# Controller_driver.net
KiCad netlist of a schematic drawn in Altium Designer
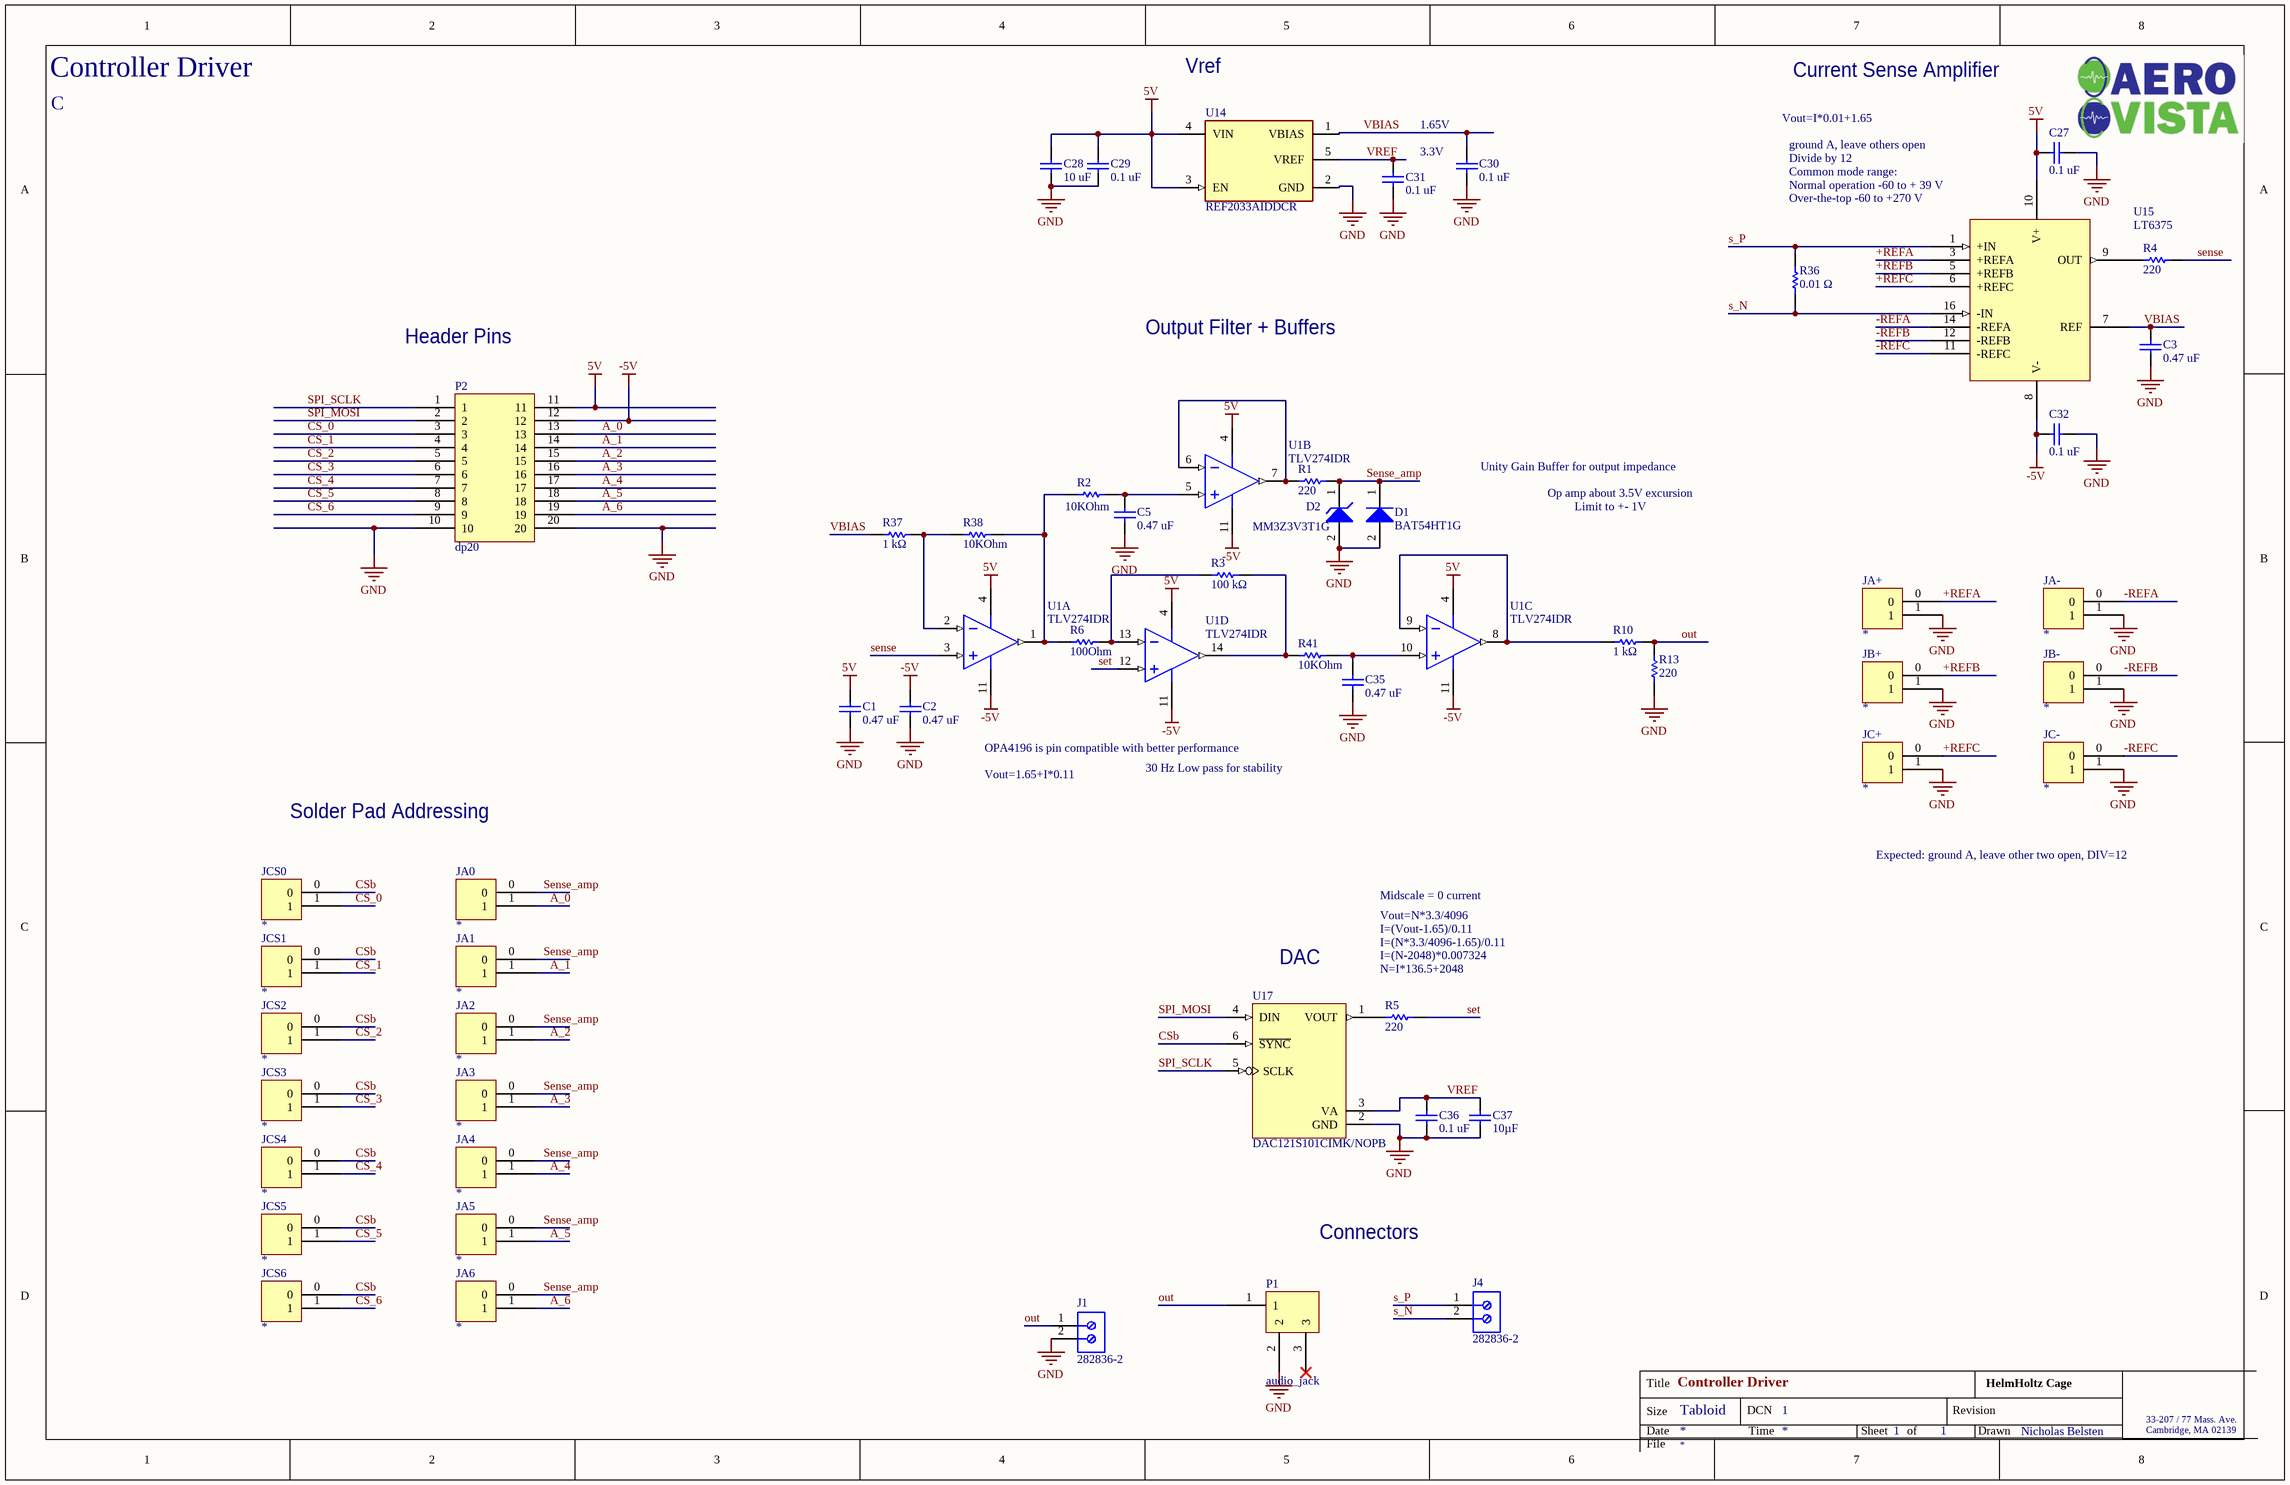
[diagram p0: Controller_driver.SchDoc]

(export (version "E")
  (design (tool "Eeschema 10.0.6"))
  (components
    (comp (ref "C1")
      (value "0.47 uF")
      (footprint "CAPC1608X90X35ML10T15")
      (fields (field (name "MANUFACTURER") "Murata") (field (name "PART NUMBER") "GRM188R71C474KA88D"))
      (libsource (lib "Altium Content Vault") (part "CAP"))
    )
    (comp (ref "C2")
      (value "0.47 uF")
      (footprint "CAPC1608X90X35ML10T15")
      (fields (field (name "MANUFACTURER") "Murata") (field (name "PART NUMBER") "GRM188R71C474KA88D"))
      (libsource (lib "Altium Content Vault") (part "CAP"))
    )
    (comp (ref "C3")
      (value "0.47 uF")
      (footprint "CAPC1608X90X35ML10T15")
      (fields (field (name "MANUFACTURER") "Murata") (field (name "PART NUMBER") "GRM188R71C474KA88D"))
      (libsource (lib "Altium Content Vault") (part "CAP"))
    )
    (comp (ref "C5")
      (value "0.47 uF")
      (footprint "CAPC1608X90X35ML10T15")
      (fields (field (name "MANUFACTURER") "Murata") (field (name "PART NUMBER") "GRM188R71C474KA88D"))
      (libsource (lib "Altium Content Vault") (part "CAP"))
    )
    (comp (ref "C27")
      (value "0.1 uF")
      (footprint "CAPC1608X87X35NL15T15")
      (fields (field (name "PART NUMBER") "C0603X104K5RACTU") (field (name "MANUFACTURER") "Kemet"))
      (libsource (lib "Altium Content Vault") (part "CAP"))
    )
    (comp (ref "C28")
      (value "10 uF")
      (footprint "CAPC1608X90X20ML10")
      (description "Chip Capacitor, 10 uF, +/- 10%, 10 V, -55 to 85 degC, 0603 (1608 Metric), RoHS, Tape and Reel")
      (fields
        (field (name "PCN PART NUMBER") "MLCCPartNumberChange30/Nov/2012")
        (field (name "TOLERANCE") "±10%")
      )
      (libsource (lib "Altium Content Vault") (part "CAP-NP-2"))
    )
    (comp (ref "C29")
      (value "0.1 uF")
      (footprint "CAPC1608X87X35NL15T15")
      (fields (field (name "PART NUMBER") "C0603X104K5RACTU") (field (name "MANUFACTURER") "Kemet"))
      (libsource (lib "Altium Content Vault") (part "CAP"))
    )
    (comp (ref "C30")
      (value "0.1 uF")
      (footprint "CAPC1608X87X35NL15T15")
      (fields (field (name "PART NUMBER") "C0603X104K5RACTU") (field (name "MANUFACTURER") "Kemet"))
      (libsource (lib "Altium Content Vault") (part "CAP"))
    )
    (comp (ref "C31")
      (value "0.1 uF")
      (footprint "CAPC1608X87X35NL15T15")
      (fields (field (name "PART NUMBER") "C0603X104K5RACTU") (field (name "MANUFACTURER") "Kemet"))
      (libsource (lib "Altium Content Vault") (part "CAP"))
    )
    (comp (ref "C32")
      (value "0.1 uF")
      (footprint "CAPC1608X87X35NL15T15")
      (fields (field (name "PART NUMBER") "C0603X104K5RACTU") (field (name "MANUFACTURER") "Kemet"))
      (libsource (lib "Altium Content Vault") (part "CAP"))
    )
    (comp (ref "C35")
      (value "0.47 uF")
      (footprint "CAPC1608X90X35ML10T15")
      (fields (field (name "MANUFACTURER") "Murata") (field (name "PART NUMBER") "GRM188R71C474KA88D"))
      (libsource (lib "Altium Content Vault") (part "CAP"))
    )
    (comp (ref "C36")
      (value "0.1 uF")
      (footprint "CAPC1608X87X35NL15T15")
      (fields (field (name "PART NUMBER") "C0603X104K5RACTU") (field (name "MANUFACTURER") "Kemet"))
      (libsource (lib "Altium Content Vault") (part "CAP"))
    )
    (comp (ref "C37")
      (value "10µF")
      (footprint "CAPC1608X90X20ML10")
      (description "Chip Capacitor, 10 uF, +/- 10%, 10 V, -55 to 85 degC, 0603 (1608 Metric), RoHS, Tape and Reel")
      (fields
        (field (name "PCN PART NUMBER") "MLCCPartNumberChange30/Nov/2012")
        (field (name "TOLERANCE") "±10%")
      )
      (libsource (lib "Altium Content Vault") (part "CAP-NP-2"))
    )
    (comp (ref "D1")
      (value "BAT54HT1G")
      (footprint "ONSC-SOD-323-2-477-02_V")
      (description "Schottky Barrier Diode, 2-Pin SOD-323, Pb-Free, Tape and Reel")
      (fields (field (name "MANUFACTURER") "On Semiconductor"))
      (libsource (lib "Altium Content Vault") (part "ONSC-D-K1A2-2"))
    )
    (comp (ref "D2")
      (value "MM3Z3V3T1G")
      (footprint "ONSC-SOD-323-2-477-02_V")
      (description "Zener Voltage Regulator, 300 mW, 2-Pin SOD-323, Pb-Free, Tape and Reel")
      (fields (field (name "MANUFACTURER") "On Semiconductor"))
      (libsource (lib "Altium Content Vault") (part "ONSC-K1A2-2"))
    )
    (comp (ref "J1")
      (value "282836-2")
      (footprint "TECO-282836-2_V")
      (description "Female Header, Pitch 5 mm, 1 x 2 Position, Height 10 mm, Tail Length 3.5 mm, Rohs, Bulk")
      (fields (field (name "VOLTAGE") "300V") (field (name "MANUFACTURER") "TE Connectivity"))
      (libsource (lib "Altium Content Vault") (part "CN-1P-F-TB2"))
    )
    (comp (ref "J4")
      (value "282836-2")
      (footprint "TECO-282836-2_V")
      (description "Female Header, Pitch 5 mm, 1 x 2 Position, Height 10 mm, Tail Length 3.5 mm, Rohs, Bulk")
      (fields (field (name "VOLTAGE") "300V") (field (name "MANUFACTURER") "TE Connectivity"))
      (libsource (lib "Altium Content Vault") (part "CN-1P-F-TB2"))
    )
    (comp (ref "JA+") (value "*") (footprint "solder_jumper") (libsource (lib "*") (part "solder_jumper")))
    (comp (ref "JA-") (value "*") (footprint "solder_jumper") (libsource (lib "*") (part "solder_jumper")))
    (comp (ref "JA0") (value "*") (footprint "solder_jumper") (libsource (lib "*") (part "solder_jumper")))
    (comp (ref "JA1") (value "*") (footprint "solder_jumper") (libsource (lib "*") (part "solder_jumper")))
    (comp (ref "JA2") (value "*") (footprint "solder_jumper") (libsource (lib "*") (part "solder_jumper")))
    (comp (ref "JA3") (value "*") (footprint "solder_jumper") (libsource (lib "*") (part "solder_jumper")))
    (comp (ref "JA4") (value "*") (footprint "solder_jumper") (libsource (lib "*") (part "solder_jumper")))
    (comp (ref "JA5") (value "*") (footprint "solder_jumper") (libsource (lib "*") (part "solder_jumper")))
    (comp (ref "JA6") (value "*") (footprint "solder_jumper") (libsource (lib "*") (part "solder_jumper")))
    (comp (ref "JB+") (value "*") (footprint "solder_jumper") (libsource (lib "*") (part "solder_jumper")))
    (comp (ref "JB-") (value "*") (footprint "solder_jumper") (libsource (lib "*") (part "solder_jumper")))
    (comp (ref "JC+") (value "*") (footprint "solder_jumper") (libsource (lib "*") (part "solder_jumper")))
    (comp (ref "JC-") (value "*") (footprint "solder_jumper") (libsource (lib "*") (part "solder_jumper")))
    (comp (ref "JCS0") (value "*") (footprint "solder_jumper") (libsource (lib "*") (part "solder_jumper")))
    (comp (ref "JCS1") (value "*") (footprint "solder_jumper") (libsource (lib "*") (part "solder_jumper")))
    (comp (ref "JCS2") (value "*") (footprint "solder_jumper") (libsource (lib "*") (part "solder_jumper")))
    (comp (ref "JCS3") (value "*") (footprint "solder_jumper") (libsource (lib "*") (part "solder_jumper")))
    (comp (ref "JCS4") (value "*") (footprint "solder_jumper") (libsource (lib "*") (part "solder_jumper")))
    (comp (ref "JCS5") (value "*") (footprint "solder_jumper") (libsource (lib "*") (part "solder_jumper")))
    (comp (ref "JCS6") (value "*") (footprint "solder_jumper") (libsource (lib "*") (part "solder_jumper")))
    (comp (ref "P1")
      (value "audio_jack")
      (footprint "MJ-3536NG")
      (libsource (lib "myComponents") (part "audio_jack"))
    )
    (comp (ref "P2")
      (value "dp20")
      (footprint "dp20-900-double")
      (libsource (lib "myComponents") (part "dp20"))
    )
    (comp (ref "R1")
      (value "220")
      (footprint "RESC1609X50X30LL10T20")
      (fields (field (name "PART NUMBER") "CRCW0603220RFKEA") (field (name "MANUFACTURER") "Vishay Dale"))
      (libsource (lib "Altium Content Vault") (part "RES"))
    )
    (comp (ref "R2")
      (value "10KOhm")
      (footprint "RESC1609X55X30LL15T15")
      (description "Chip Resistor, 10 KOhm, +/- 1%, 0.1 W, -55 to 155 degC, 0603 (1608 Metric), RoHS, Tape and Reel")
      (fields (field (name "TOLERANCE") "1%") (field (name "MANUFACTURER") "Panasonic"))
      (libsource (lib "Altium Content Vault") (part "RES-2"))
    )
    (comp (ref "R3")
      (value "100 kΩ")
      (footprint "RESC1608X55X25NL10T15")
      (fields (field (name "PART NUMBER") "RC0603JR-10100KL") (field (name "MANUFACTURER") "Yageo"))
      (libsource (lib "Altium Content Vault") (part "RES"))
    )
    (comp (ref "R4")
      (value "220")
      (footprint "RESC1609X50X30LL10T20")
      (fields (field (name "PART NUMBER") "CRCW0603220RFKEA") (field (name "MANUFACTURER") "Vishay Dale"))
      (libsource (lib "Altium Content Vault") (part "RES"))
    )
    (comp (ref "R5")
      (value "220")
      (footprint "RESC1609X50X30LL10T20")
      (fields (field (name "PART NUMBER") "CRCW0603220RFKEA") (field (name "MANUFACTURER") "Vishay Dale"))
      (libsource (lib "Altium Content Vault") (part "RES"))
    )
    (comp (ref "R6")
      (value "100Ohm")
      (footprint "RESC1608X55X25NL10T15")
      (description "Chip Resistor, 100 Ohm, +/- 1%, 0.1 W, -55 to 155 degC, 0603 (1608 Metric), RoHS, Tape and Reel")
      (fields (field (name "TOLERANCE") "1%") (field (name "MANUFACTURER") "Yageo"))
      (libsource (lib "Altium Content Vault") (part "RES-2"))
    )
    (comp (ref "R10")
      (value "1 kΩ")
      (footprint "RESC1608X55X30LL20T20")
      (fields (field (name "MANUFACTURER") "Panasonic") (field (name "PART NUMBER") "ERA3AEB102V"))
      (libsource (lib "Altium Content Vault") (part "RES"))
    )
    (comp (ref "R13")
      (value "220")
      (footprint "RESC1609X50X30LL10T20")
      (fields (field (name "PART NUMBER") "CRCW0603220RFKEA") (field (name "MANUFACTURER") "Vishay Dale"))
      (libsource (lib "Altium Content Vault") (part "RES"))
    )
    (comp (ref "R36")
      (value "0.01 Ω")
      (footprint "RESC3216X70X50LL05T20")
      (fields (field (name "PART NUMBER") "ERJ8BWFR010V") (field (name "MANUFACTURER") "Panasonic"))
      (libsource (lib "Altium Content Vault") (part "RES"))
    )
    (comp (ref "R37")
      (value "1 kΩ")
      (footprint "RESC1608X55X30LL15T15")
      (fields (field (name "PART NUMBER") "ERJ-3EKF1001V") (field (name "MANUFACTURER") "Panasonic"))
      (libsource (lib "Altium Content Vault") (part "RES"))
    )
    (comp (ref "R38")
      (value "10KOhm")
      (footprint "RESC1609X55X30LL15T15")
      (description "Chip Resistor, 10 KOhm, +/- 1%, 0.1 W, -55 to 155 degC, 0603 (1608 Metric), RoHS, Tape and Reel")
      (fields (field (name "TOLERANCE") "1%") (field (name "MANUFACTURER") "Panasonic"))
      (libsource (lib "Altium Content Vault") (part "RES-2"))
    )
    (comp (ref "R41")
      (value "10KOhm")
      (footprint "RESC1609X55X30LL15T15")
      (description "Chip Resistor, 10 KOhm, +/- 1%, 0.1 W, -55 to 155 degC, 0603 (1608 Metric), RoHS, Tape and Reel")
      (fields (field (name "TOLERANCE") "1%") (field (name "MANUFACTURER") "Panasonic"))
      (libsource (lib "Altium Content Vault") (part "RES-2"))
    )
    (comp (ref "U1")
      (value "TLV274IDR")
      (footprint "D0014A_N")
      (fields (field (name "MANUFACTURER") "Texas Instruments"))
      (libsource (lib "Altium Content Vault") (part "TI-TLC_TLV_TLC1079-14"))
    )
    (comp (ref "U14")
      (value "REF2033AIDDCR")
      (footprint "FP-DDC0005A-MFG")
      (description "IC VREF SERIES 1.65V/3.3V 5SOT")
      (fields
        (field (name "OCTOPART") "https://octopart.com/ref2033aiddcr-texas+instruments-46921199")
        (field (name "MANUFACTURER") "Texas Instruments")
      )
      (libsource (lib "Altium Content Vault") (part "d9fc07eafd300fec854b4093a15f761"))
    )
    (comp (ref "U15")
      (value "LT6375")
      (footprint "SOP16-12")
      (libsource (lib "myComponents") (part "LT6375"))
    )
    (comp (ref "U17")
      (value "DAC121S101CIMK/NOPB")
      (footprint "MK06A_N")
      (description "12-Bit Micro Power, RRO Digital-to-Analog Converter, 6-pin Tiny SOT23, Pb-Free")
      (fields (field (name "MANUFACTURER") "National Semiconductor"))
      (libsource (lib "Altium Content Vault") (part "CON-DAC-DAC121S101-6"))
    )
  )
  (nets
    (net (code "1") (name "-5V") (class "Default")
      (node (ref "C2") (pin "2") (pinfunction "2_2") (pintype "passive"))
      (node (ref "C32") (pin "2") (pinfunction "2_2") (pintype "passive"))
      (node (ref "P2") (pin "12") (pinfunction "12_12") (pintype "passive"))
      (node (ref "U1") (pin "11") (pinfunction "GND_11") (pintype "power_in"))
      (node (ref "U15") (pin "8") (pinfunction "V-_8") (pintype "power_in"))
    )
    (net (code "2") (name "/+REFA") (class "Default")
      (node (ref "JA+") (pin "0") (pinfunction "0_0") (pintype "passive"))
      (node (ref "U15") (pin "3") (pinfunction "+REFA_3") (pintype "passive"))
    )
    (net (code "3") (name "/+REFB") (class "Default")
      (node (ref "JB+") (pin "0") (pinfunction "0_0") (pintype "passive"))
      (node (ref "U15") (pin "5") (pinfunction "+REFB_5") (pintype "passive"))
    )
    (net (code "4") (name "/+REFC") (class "Default")
      (node (ref "JC+") (pin "0") (pinfunction "0_0") (pintype "passive"))
      (node (ref "U15") (pin "6") (pinfunction "+REFC_6") (pintype "passive"))
    )
    (net (code "5") (name "/-REFA") (class "Default")
      (node (ref "JA-") (pin "0") (pinfunction "0_0") (pintype "passive"))
      (node (ref "U15") (pin "14") (pinfunction "-REFA_14") (pintype "passive"))
    )
    (net (code "6") (name "/-REFB") (class "Default")
      (node (ref "JB-") (pin "0") (pinfunction "0_0") (pintype "passive"))
      (node (ref "U15") (pin "12") (pinfunction "-REFB_12") (pintype "passive"))
    )
    (net (code "7") (name "/-REFC") (class "Default")
      (node (ref "JC-") (pin "0") (pinfunction "0_0") (pintype "passive"))
      (node (ref "U15") (pin "11") (pinfunction "-REFC_11") (pintype "passive"))
    )
    (net (code "8") (name "/A_0") (class "Default")
      (node (ref "JA0") (pin "1") (pinfunction "1_1") (pintype "passive"))
      (node (ref "P2") (pin "13") (pinfunction "13_13") (pintype "passive"))
    )
    (net (code "9") (name "/A_1") (class "Default")
      (node (ref "JA1") (pin "1") (pinfunction "1_1") (pintype "passive"))
      (node (ref "P2") (pin "14") (pinfunction "14_14") (pintype "passive"))
    )
    (net (code "10") (name "/A_2") (class "Default")
      (node (ref "JA2") (pin "1") (pinfunction "1_1") (pintype "passive"))
      (node (ref "P2") (pin "15") (pinfunction "15_15") (pintype "passive"))
    )
    (net (code "11") (name "/A_3") (class "Default")
      (node (ref "JA3") (pin "1") (pinfunction "1_1") (pintype "passive"))
      (node (ref "P2") (pin "16") (pinfunction "16_16") (pintype "passive"))
    )
    (net (code "12") (name "/A_4") (class "Default")
      (node (ref "JA4") (pin "1") (pinfunction "1_1") (pintype "passive"))
      (node (ref "P2") (pin "17") (pinfunction "17_17") (pintype "passive"))
    )
    (net (code "13") (name "/A_5") (class "Default")
      (node (ref "JA5") (pin "1") (pinfunction "1_1") (pintype "passive"))
      (node (ref "P2") (pin "18") (pinfunction "18_18") (pintype "passive"))
    )
    (net (code "14") (name "/A_6") (class "Default")
      (node (ref "JA6") (pin "1") (pinfunction "1_1") (pintype "passive"))
      (node (ref "P2") (pin "19") (pinfunction "19_19") (pintype "passive"))
    )
    (net (code "15") (name "/CS_0") (class "Default")
      (node (ref "JCS0") (pin "1") (pinfunction "1_1") (pintype "passive"))
      (node (ref "P2") (pin "3") (pinfunction "3_3") (pintype "passive"))
    )
    (net (code "16") (name "/CS_1") (class "Default")
      (node (ref "JCS1") (pin "1") (pinfunction "1_1") (pintype "passive"))
      (node (ref "P2") (pin "4") (pinfunction "4_4") (pintype "passive"))
    )
    (net (code "17") (name "/CS_2") (class "Default")
      (node (ref "JCS2") (pin "1") (pinfunction "1_1") (pintype "passive"))
      (node (ref "P2") (pin "5") (pinfunction "5_5") (pintype "passive"))
    )
    (net (code "18") (name "/CS_3") (class "Default")
      (node (ref "JCS3") (pin "1") (pinfunction "1_1") (pintype "passive"))
      (node (ref "P2") (pin "6") (pinfunction "6_6") (pintype "passive"))
    )
    (net (code "19") (name "/CS_4") (class "Default")
      (node (ref "JCS4") (pin "1") (pinfunction "1_1") (pintype "passive"))
      (node (ref "P2") (pin "7") (pinfunction "7_7") (pintype "passive"))
    )
    (net (code "20") (name "/CS_5") (class "Default")
      (node (ref "JCS5") (pin "1") (pinfunction "1_1") (pintype "passive"))
      (node (ref "P2") (pin "8") (pinfunction "8_8") (pintype "passive"))
    )
    (net (code "21") (name "/CS_6") (class "Default")
      (node (ref "JCS6") (pin "1") (pinfunction "1_1") (pintype "passive"))
      (node (ref "P2") (pin "9") (pinfunction "9_9") (pintype "passive"))
    )
    (net (code "22") (name "/CSb") (class "Default")
      (node (ref "JCS0") (pin "0") (pinfunction "0_0") (pintype "passive"))
      (node (ref "JCS1") (pin "0") (pinfunction "0_0") (pintype "passive"))
      (node (ref "JCS2") (pin "0") (pinfunction "0_0") (pintype "passive"))
      (node (ref "JCS3") (pin "0") (pinfunction "0_0") (pintype "passive"))
      (node (ref "JCS4") (pin "0") (pinfunction "0_0") (pintype "passive"))
      (node (ref "JCS5") (pin "0") (pinfunction "0_0") (pintype "passive"))
      (node (ref "JCS6") (pin "0") (pinfunction "0_0") (pintype "passive"))
      (node (ref "U17") (pin "6") (pinfunction "~{SYNC}_6") (pintype "input"))
    )
    (net (code "23") (name "/SPI_MOSI") (class "Default")
      (node (ref "P2") (pin "2") (pinfunction "2_2") (pintype "passive"))
      (node (ref "U17") (pin "4") (pinfunction "DIN_4") (pintype "input"))
    )
    (net (code "24") (name "/SPI_SCLK") (class "Default")
      (node (ref "P2") (pin "1") (pinfunction "1_1") (pintype "passive"))
      (node (ref "U17") (pin "5") (pinfunction "SCLK_5") (pintype "input"))
    )
    (net (code "25") (name "/Sense_amp") (class "Default")
      (node (ref "D1") (pin "1") (pinfunction "K_1") (pintype "passive"))
      (node (ref "D2") (pin "1") (pinfunction "K_1") (pintype "passive"))
      (node (ref "JA0") (pin "0") (pinfunction "0_0") (pintype "passive"))
      (node (ref "JA1") (pin "0") (pinfunction "0_0") (pintype "passive"))
      (node (ref "JA2") (pin "0") (pinfunction "0_0") (pintype "passive"))
      (node (ref "JA3") (pin "0") (pinfunction "0_0") (pintype "passive"))
      (node (ref "JA4") (pin "0") (pinfunction "0_0") (pintype "passive"))
      (node (ref "JA5") (pin "0") (pinfunction "0_0") (pintype "passive"))
      (node (ref "JA6") (pin "0") (pinfunction "0_0") (pintype "passive"))
      (node (ref "R1") (pin "2") (pinfunction "2_2") (pintype "passive"))
    )
    (net (code "26") (name "/VBIAS") (class "Default")
      (node (ref "C3") (pin "2") (pinfunction "2_2") (pintype "passive"))
      (node (ref "C30") (pin "2") (pinfunction "2_2") (pintype "passive"))
      (node (ref "R37") (pin "2") (pinfunction "2_2") (pintype "passive"))
      (node (ref "U14") (pin "1") (pinfunction "VBIAS_1") (pintype "power_in"))
      (node (ref "U15") (pin "7") (pinfunction "REF_7") (pintype "passive"))
    )
    (net (code "27") (name "/VREF") (class "Default")
      (node (ref "C31") (pin "2") (pinfunction "2_2") (pintype "passive"))
      (node (ref "C36") (pin "2") (pinfunction "2_2") (pintype "passive"))
      (node (ref "C37") (pin "2") (pinfunction "2_2") (pintype "passive"))
      (node (ref "U14") (pin "5") (pinfunction "VREF_5") (pintype "power_in"))
      (node (ref "U17") (pin "3") (pinfunction "VA_3") (pintype "power_in"))
    )
    (net (code "28") (name "/out") (class "Default")
      (node (ref "J1") (pin "1") (pinfunction "1_1") (pintype "passive"))
      (node (ref "P1") (pin "1") (pinfunction "1_1") (pintype "passive"))
      (node (ref "R10") (pin "2") (pinfunction "2_2") (pintype "passive"))
      (node (ref "R13") (pin "2") (pinfunction "2_2") (pintype "passive"))
    )
    (net (code "29") (name "/s_N") (class "Default")
      (node (ref "J4") (pin "2") (pinfunction "2_2") (pintype "passive"))
      (node (ref "R36") (pin "1") (pinfunction "1_1") (pintype "passive"))
      (node (ref "U15") (pin "16") (pinfunction "-IN_16") (pintype "input"))
    )
    (net (code "30") (name "/s_P") (class "Default")
      (node (ref "J4") (pin "1") (pinfunction "1_1") (pintype "passive"))
      (node (ref "R36") (pin "2") (pinfunction "2_2") (pintype "passive"))
      (node (ref "U15") (pin "1") (pinfunction "+IN_1") (pintype "input"))
    )
    (net (code "31") (name "/sense") (class "Default")
      (node (ref "R4") (pin "2") (pinfunction "2_2") (pintype "passive"))
      (node (ref "U1") (pin "3") (pinfunction "IN1+_3") (pintype "input"))
    )
    (net (code "32") (name "/set") (class "Default")
      (node (ref "R5") (pin "2") (pinfunction "2_2") (pintype "passive"))
      (node (ref "U1") (pin "12") (pinfunction "IN4+_12") (pintype "input"))
    )
    (net (code "33") (name "5V") (class "Default")
      (node (ref "C1") (pin "2") (pinfunction "2_2") (pintype "passive"))
      (node (ref "C27") (pin "2") (pinfunction "2_2") (pintype "passive"))
      (node (ref "C28") (pin "2") (pinfunction "2_2") (pintype "passive"))
      (node (ref "C29") (pin "2") (pinfunction "2_2") (pintype "passive"))
      (node (ref "P2") (pin "11") (pinfunction "11_11") (pintype "passive"))
      (node (ref "U1") (pin "4") (pinfunction "VDD_4") (pintype "power_in"))
      (node (ref "U14") (pin "3") (pinfunction "EN_3") (pintype "input"))
      (node (ref "U14") (pin "4") (pinfunction "VIN_4") (pintype "power_in"))
      (node (ref "U15") (pin "10") (pinfunction "V+_10") (pintype "power_in"))
    )
    (net (code "34") (name "GND") (class "Default")
      (node (ref "C1") (pin "1") (pinfunction "1_1") (pintype "passive"))
      (node (ref "C2") (pin "1") (pinfunction "1_1") (pintype "passive"))
      (node (ref "C27") (pin "1") (pinfunction "1_1") (pintype "passive"))
      (node (ref "C28") (pin "1") (pinfunction "1_1") (pintype "passive"))
      (node (ref "C29") (pin "1") (pinfunction "1_1") (pintype "passive"))
      (node (ref "C3") (pin "1") (pinfunction "1_1") (pintype "passive"))
      (node (ref "C30") (pin "1") (pinfunction "1_1") (pintype "passive"))
      (node (ref "C31") (pin "1") (pinfunction "1_1") (pintype "passive"))
      (node (ref "C32") (pin "1") (pinfunction "1_1") (pintype "passive"))
      (node (ref "C35") (pin "1") (pinfunction "1_1") (pintype "passive"))
      (node (ref "C36") (pin "1") (pinfunction "1_1") (pintype "passive"))
      (node (ref "C37") (pin "1") (pinfunction "1_1") (pintype "passive"))
      (node (ref "C5") (pin "1") (pinfunction "1_1") (pintype "passive"))
      (node (ref "D1") (pin "2") (pinfunction "A_2") (pintype "passive"))
      (node (ref "D2") (pin "2") (pinfunction "A_2") (pintype "passive"))
      (node (ref "J1") (pin "2") (pinfunction "2_2") (pintype "passive"))
      (node (ref "JA+") (pin "1") (pinfunction "1_1") (pintype "passive"))
      (node (ref "JA-") (pin "1") (pinfunction "1_1") (pintype "passive"))
      (node (ref "JB+") (pin "1") (pinfunction "1_1") (pintype "passive"))
      (node (ref "JB-") (pin "1") (pinfunction "1_1") (pintype "passive"))
      (node (ref "JC+") (pin "1") (pinfunction "1_1") (pintype "passive"))
      (node (ref "JC-") (pin "1") (pinfunction "1_1") (pintype "passive"))
      (node (ref "P1") (pin "2") (pinfunction "2_2") (pintype "passive"))
      (node (ref "P2") (pin "10") (pinfunction "10_10") (pintype "passive"))
      (node (ref "P2") (pin "20") (pinfunction "20_20") (pintype "passive"))
      (node (ref "R13") (pin "1") (pinfunction "1_1") (pintype "passive"))
      (node (ref "U14") (pin "2") (pinfunction "GND_2") (pintype "power_in"))
      (node (ref "U17") (pin "2") (pinfunction "GND_2") (pintype "power_in"))
    )
    (net (code "35") (name "Net-(U1A-IN1-)") (class "Default")
      (node (ref "R37") (pin "1") (pinfunction "1_1") (pintype "passive"))
      (node (ref "R38") (pin "1") (pinfunction "1_1") (pintype "passive"))
      (node (ref "U1") (pin "2") (pinfunction "IN1-_2") (pintype "input"))
    )
    (net (code "36") (name "Net-(U1A-OUT1)") (class "Default")
      (node (ref "R2") (pin "1") (pinfunction "1_1") (pintype "passive"))
      (node (ref "R38") (pin "2") (pinfunction "2_2") (pintype "passive"))
      (node (ref "R6") (pin "1") (pinfunction "1_1") (pintype "passive"))
      (node (ref "U1") (pin "1") (pinfunction "OUT1_1") (pintype "output"))
    )
    (net (code "37") (name "Net-(U1B-IN2+)") (class "Default")
      (node (ref "C5") (pin "2") (pinfunction "2_2") (pintype "passive"))
      (node (ref "R2") (pin "2") (pinfunction "2_2") (pintype "passive"))
      (node (ref "U1") (pin "5") (pinfunction "IN2+_5") (pintype "input"))
    )
    (net (code "38") (name "Net-(U1B-IN2-)") (class "Default")
      (node (ref "R1") (pin "1") (pinfunction "1_1") (pintype "passive"))
      (node (ref "U1") (pin "6") (pinfunction "IN2-_6") (pintype "input"))
      (node (ref "U1") (pin "7") (pinfunction "OUT2_7") (pintype "output"))
    )
    (net (code "39") (name "Net-(U1C-IN3+)") (class "Default")
      (node (ref "C35") (pin "2") (pinfunction "2_2") (pintype "passive"))
      (node (ref "R41") (pin "2") (pinfunction "2_2") (pintype "passive"))
      (node (ref "U1") (pin "10") (pinfunction "IN3+_10") (pintype "input"))
    )
    (net (code "40") (name "Net-(U1C-IN3-)") (class "Default")
      (node (ref "R10") (pin "1") (pinfunction "1_1") (pintype "passive"))
      (node (ref "U1") (pin "8") (pinfunction "OUT3_8") (pintype "output"))
      (node (ref "U1") (pin "9") (pinfunction "IN3-_9") (pintype "input"))
    )
    (net (code "41") (name "Net-(U1D-IN4-)") (class "Default")
      (node (ref "R3") (pin "2") (pinfunction "2_2") (pintype "passive"))
      (node (ref "R6") (pin "2") (pinfunction "2_2") (pintype "passive"))
      (node (ref "U1") (pin "13") (pinfunction "IN4-_13") (pintype "input"))
    )
    (net (code "42") (name "Net-(U1D-OUT4)") (class "Default")
      (node (ref "R3") (pin "1") (pinfunction "1_1") (pintype "passive"))
      (node (ref "R41") (pin "1") (pinfunction "1_1") (pintype "passive"))
      (node (ref "U1") (pin "14") (pinfunction "OUT4_14") (pintype "output"))
    )
    (net (code "43") (name "Net-(U15-OUT)") (class "Default")
      (node (ref "R4") (pin "1") (pinfunction "1_1") (pintype "passive"))
      (node (ref "U15") (pin "9") (pinfunction "OUT_9") (pintype "output"))
    )
    (net (code "44") (name "Net-(U17-VOUT)") (class "Default")
      (node (ref "R5") (pin "1") (pinfunction "1_1") (pintype "passive"))
      (node (ref "U17") (pin "1") (pinfunction "VOUT_1") (pintype "output"))
    )
    (net (code "45") (name "unconnected-(P1-Pad3)") (class "Default")
      (node (ref "P1") (pin "3") (pinfunction "3_3") (pintype "passive+no_connect"))
    )
  )
)
